# BSPD_REV2.net
KiCad netlist of a schematic drawn in EAGLE
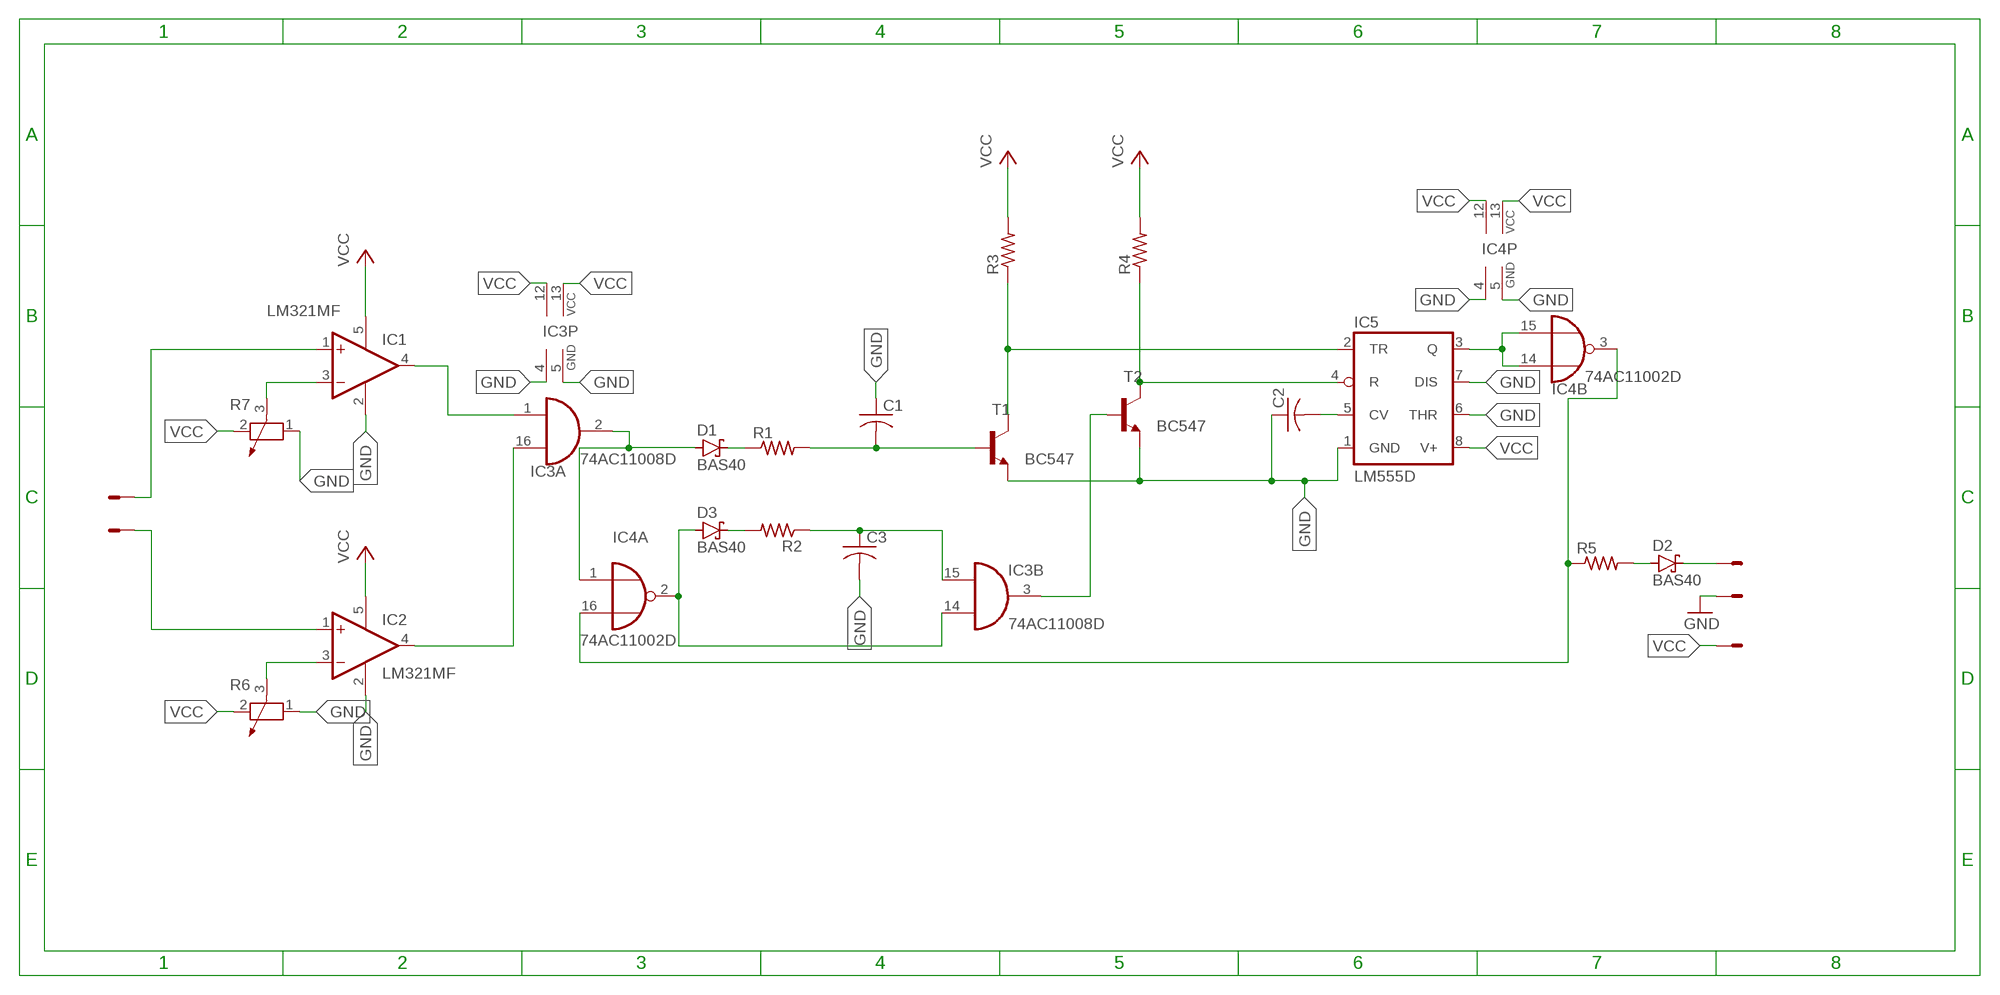
[diagram p0: schematic, sheet 1]

(export (version "E")
  (design (tool "Eeschema 10.0.6"))
  (components
    (comp (ref "C1")
      (value "C-USC0402")
      (footprint "eagle-import:C0402")
      (libsource (lib "eagle-import") (part "C-USC0402"))
    )
    (comp (ref "C2")
      (value "C-USC0402")
      (footprint "eagle-import:C0402")
      (libsource (lib "eagle-import") (part "C-USC0402"))
    )
    (comp (ref "C3")
      (value "C-USC0402")
      (footprint "eagle-import:C0402")
      (libsource (lib "eagle-import") (part "C-USC0402"))
    )
    (comp (ref "D1")
      (value "BAS40")
      (footprint "eagle-import:SOT23")
      (libsource (lib "eagle-import") (part "BAS40"))
    )
    (comp (ref "D2")
      (value "BAS40")
      (footprint "eagle-import:SOT23")
      (libsource (lib "eagle-import") (part "BAS40"))
    )
    (comp (ref "D3")
      (value "BAS40")
      (footprint "eagle-import:SOT23")
      (libsource (lib "eagle-import") (part "BAS40"))
    )
    (comp (ref "IC1")
      (value "LM321MF")
      (footprint "eagle-import:SOT23-5")
      (libsource (lib "eagle-import") (part "LM321?MF"))
    )
    (comp (ref "IC2")
      (value "LM321MF")
      (footprint "eagle-import:SOT23-5")
      (libsource (lib "eagle-import") (part "LM321?MF"))
    )
    (comp (ref "IC3")
      (value "74AC11008D")
      (footprint "eagle-import:SO16")
      (libsource (lib "eagle-import") (part "74AC11008D"))
    )
    (comp (ref "IC4")
      (value "74AC11002D")
      (footprint "eagle-import:SO16")
      (libsource (lib "eagle-import") (part "74AC11002D"))
    )
    (comp (ref "IC5")
      (value "LM555D")
      (footprint "eagle-import:SO08")
      (libsource (lib "eagle-import") (part "555DLM"))
    )
    (comp (ref "R1")
      (value "R-US_M1406")
      (footprint "eagle-import:M1406")
      (libsource (lib "eagle-import") (part "R-US_M1406"))
    )
    (comp (ref "R2")
      (value "R-US_M1406")
      (footprint "eagle-import:M1406")
      (libsource (lib "eagle-import") (part "R-US_M1406"))
    )
    (comp (ref "R3")
      (value "R-US_M1406")
      (footprint "eagle-import:M1406")
      (libsource (lib "eagle-import") (part "R-US_M1406"))
    )
    (comp (ref "R4")
      (value "R-US_M1406")
      (footprint "eagle-import:M1406")
      (libsource (lib "eagle-import") (part "R-US_M1406"))
    )
    (comp (ref "R5")
      (value "R-US_M1406")
      (footprint "eagle-import:M1406")
      (libsource (lib "eagle-import") (part "R-US_M1406"))
    )
    (comp (ref "R6")
      (value "POTENTIOMETER_PT_SPIN")
      (footprint "eagle-import:PT-SPIN")
      (libsource (lib "eagle-import") (part "POTENTIOMETER_PT_SPIN"))
    )
    (comp (ref "R7")
      (value "POTENTIOMETER_PT_SPIN")
      (footprint "eagle-import:PT-SPIN")
      (libsource (lib "eagle-import") (part "POTENTIOMETER_PT_SPIN"))
    )
    (comp (ref "T1")
      (value "BC547")
      (footprint "eagle-import:TO92")
      (libsource (lib "eagle-import") (part "BC547"))
    )
    (comp (ref "T2")
      (value "BC547")
      (footprint "eagle-import:TO92")
      (libsource (lib "eagle-import") (part "BC547"))
    )
    (comp (ref "X1")
      (value "22-23-2051")
      (footprint "eagle-import:22-23-2051")
      (fields (field (name "MF") "MOLEX"))
      (libsource (lib "eagle-import") (part "22-23-2051"))
    )
  )
  (nets
    (net (code "1") (name "GND") (class "Default")
      (node (ref "C1") (pin "1") (pinfunction "1_1") (pintype "passive"))
      (node (ref "C2") (pin "1") (pinfunction "1_1") (pintype "passive"))
      (node (ref "C3") (pin "2") (pinfunction "2_2") (pintype "passive"))
      (node (ref "IC1") (pin "2") (pinfunction "V-_2") (pintype "power_in"))
      (node (ref "IC2") (pin "2") (pinfunction "V-_2") (pintype "power_in"))
      (node (ref "IC3") (pin "4") (pinfunction "GND_4") (pintype "power_in"))
      (node (ref "IC3") (pin "5") (pinfunction "GND_5") (pintype "power_in"))
      (node (ref "IC4") (pin "4") (pinfunction "GND_4") (pintype "power_in"))
      (node (ref "IC4") (pin "5") (pinfunction "GND_5") (pintype "power_in"))
      (node (ref "IC5") (pin "1") (pinfunction "GND_1") (pintype "power_in"))
      (node (ref "IC5") (pin "6") (pinfunction "THR_6") (pintype "input"))
      (node (ref "IC5") (pin "7") (pinfunction "DIS_7") (pintype "input"))
      (node (ref "R6") (pin "1") (pinfunction "1_1") (pintype "passive"))
      (node (ref "R7") (pin "1") (pinfunction "1_1") (pintype "passive"))
      (node (ref "T1") (pin "1") (pinfunction "E_1") (pintype "passive"))
      (node (ref "T2") (pin "1") (pinfunction "E_1") (pintype "passive"))
      (node (ref "X1") (pin "2") (pinfunction "S_2") (pintype "passive"))
    )
    (net (code "2") (name "Net-(D1-A)") (class "Default")
      (node (ref "D1") (pin "1") (pinfunction "A_1") (pintype "passive"))
      (node (ref "IC3") (pin "2") (pinfunction "O_2") (pintype "output"))
      (node (ref "IC4") (pin "1") (pinfunction "I0_1") (pintype "input"))
    )
    (net (code "3") (name "Net-(D1-C)") (class "Default")
      (node (ref "D1") (pin "3") (pinfunction "C_3") (pintype "passive"))
      (node (ref "R1") (pin "1") (pinfunction "1_1") (pintype "passive"))
    )
    (net (code "4") (name "Net-(D2-A)") (class "Default")
      (node (ref "D2") (pin "1") (pinfunction "A_1") (pintype "passive"))
      (node (ref "R5") (pin "2") (pinfunction "2_2") (pintype "passive"))
    )
    (net (code "5") (name "Net-(D2-C)") (class "Default")
      (node (ref "D2") (pin "3") (pinfunction "C_3") (pintype "passive"))
      (node (ref "X1") (pin "1") (pinfunction "S_1") (pintype "passive"))
    )
    (net (code "6") (name "Net-(D3-A)") (class "Default")
      (node (ref "D3") (pin "1") (pinfunction "A_1") (pintype "passive"))
      (node (ref "IC3") (pin "14") (pinfunction "I1_14") (pintype "input"))
      (node (ref "IC4") (pin "2") (pinfunction "O_2") (pintype "output"))
    )
    (net (code "7") (name "Net-(D3-C)") (class "Default")
      (node (ref "D3") (pin "3") (pinfunction "C_3") (pintype "passive"))
      (node (ref "R2") (pin "2") (pinfunction "2_2") (pintype "passive"))
    )
    (net (code "8") (name "Net-(IC1-+IN)") (class "Default")
      (node (ref "IC1") (pin "1") (pinfunction "+IN_1") (pintype "input"))
      (node (ref "X1") (pin "3") (pinfunction "S_3") (pintype "passive"))
    )
    (net (code "9") (name "Net-(IC1--IN)") (class "Default")
      (node (ref "IC1") (pin "3") (pinfunction "-IN_3") (pintype "input"))
      (node (ref "R7") (pin "3") (pinfunction "3_3") (pintype "passive"))
    )
    (net (code "10") (name "Net-(IC1-OUT)") (class "Default")
      (node (ref "IC1") (pin "4") (pinfunction "OUT_4") (pintype "output"))
      (node (ref "IC3") (pin "1") (pinfunction "I0_1") (pintype "input"))
    )
    (net (code "11") (name "Net-(IC2-+IN)") (class "Default")
      (node (ref "IC2") (pin "1") (pinfunction "+IN_1") (pintype "input"))
      (node (ref "X1") (pin "4") (pinfunction "S_4") (pintype "passive"))
    )
    (net (code "12") (name "Net-(IC2--IN)") (class "Default")
      (node (ref "IC2") (pin "3") (pinfunction "-IN_3") (pintype "input"))
      (node (ref "R6") (pin "3") (pinfunction "3_3") (pintype "passive"))
    )
    (net (code "13") (name "Net-(IC2-OUT)") (class "Default")
      (node (ref "IC2") (pin "4") (pinfunction "OUT_4") (pintype "output"))
      (node (ref "IC3") (pin "16") (pinfunction "I1_16") (pintype "input"))
    )
    (net (code "14") (name "Net-(IC3B-I0)") (class "Default")
      (node (ref "C3") (pin "1") (pinfunction "1_1") (pintype "passive"))
      (node (ref "IC3") (pin "15") (pinfunction "I0_15") (pintype "input"))
      (node (ref "R2") (pin "1") (pinfunction "1_1") (pintype "passive"))
    )
    (net (code "15") (name "Net-(IC3B-O)") (class "Default")
      (node (ref "IC3") (pin "3") (pinfunction "O_3") (pintype "output"))
      (node (ref "T2") (pin "2") (pinfunction "B_2") (pintype "passive"))
    )
    (net (code "16") (name "Net-(IC4A-I1)") (class "Default")
      (node (ref "IC4") (pin "16") (pinfunction "I1_16") (pintype "input"))
      (node (ref "IC4") (pin "3") (pinfunction "O_3") (pintype "output"))
      (node (ref "R5") (pin "1") (pinfunction "1_1") (pintype "passive"))
    )
    (net (code "17") (name "Net-(IC4B-I0)") (class "Default")
      (node (ref "IC4") (pin "14") (pinfunction "I1_14") (pintype "input"))
      (node (ref "IC4") (pin "15") (pinfunction "I0_15") (pintype "input"))
      (node (ref "IC5") (pin "3") (pinfunction "Q_3") (pintype "output"))
    )
    (net (code "18") (name "Net-(IC5-CV)") (class "Default")
      (node (ref "C2") (pin "2") (pinfunction "2_2") (pintype "passive"))
      (node (ref "IC5") (pin "5") (pinfunction "CV_5") (pintype "input"))
    )
    (net (code "19") (name "Net-(IC5-R)") (class "Default")
      (node (ref "IC5") (pin "4") (pinfunction "R_4") (pintype "input"))
      (node (ref "R4") (pin "1") (pinfunction "1_1") (pintype "passive"))
      (node (ref "T2") (pin "3") (pinfunction "C_3") (pintype "passive"))
    )
    (net (code "20") (name "Net-(IC5-TR)") (class "Default")
      (node (ref "IC5") (pin "2") (pinfunction "TR_2") (pintype "input"))
      (node (ref "R3") (pin "1") (pinfunction "1_1") (pintype "passive"))
      (node (ref "T1") (pin "3") (pinfunction "C_3") (pintype "passive"))
    )
    (net (code "21") (name "Net-(T1-B)") (class "Default")
      (node (ref "C1") (pin "2") (pinfunction "2_2") (pintype "passive"))
      (node (ref "R1") (pin "2") (pinfunction "2_2") (pintype "passive"))
      (node (ref "T1") (pin "2") (pinfunction "B_2") (pintype "passive"))
    )
    (net (code "22") (name "VCC") (class "Default")
      (node (ref "IC1") (pin "5") (pinfunction "V+_5") (pintype "power_in"))
      (node (ref "IC2") (pin "5") (pinfunction "V+_5") (pintype "power_in"))
      (node (ref "IC3") (pin "12") (pinfunction "VCC_12") (pintype "power_in"))
      (node (ref "IC3") (pin "13") (pinfunction "VCC_13") (pintype "power_in"))
      (node (ref "IC4") (pin "12") (pinfunction "VCC_12") (pintype "power_in"))
      (node (ref "IC4") (pin "13") (pinfunction "VCC_13") (pintype "power_in"))
      (node (ref "IC5") (pin "8") (pinfunction "V+_8") (pintype "power_in"))
      (node (ref "R3") (pin "2") (pinfunction "2_2") (pintype "passive"))
      (node (ref "R4") (pin "2") (pinfunction "2_2") (pintype "passive"))
      (node (ref "R6") (pin "2") (pinfunction "2_2") (pintype "passive"))
      (node (ref "R7") (pin "2") (pinfunction "2_2") (pintype "passive"))
      (node (ref "X1") (pin "5") (pinfunction "S_5") (pintype "passive"))
    )
  )
)
